# 04_POWER_LDO.net
KiCad netlist of a schematic drawn in Altium Designer
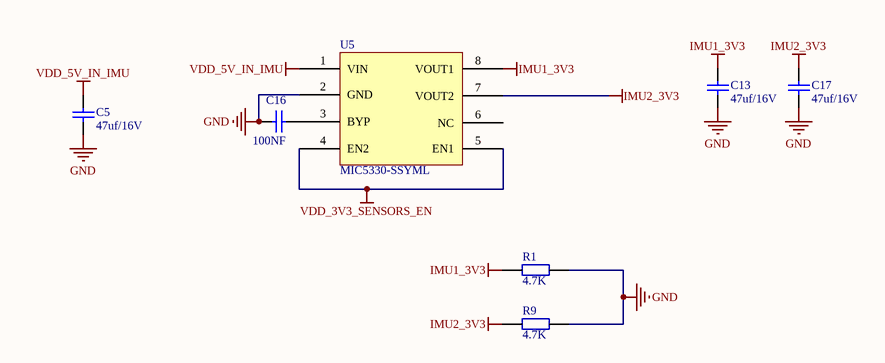
[diagram p0: 04_POWER_LDO.SchDoc]

(export (version "E")
  (design (tool "Eeschema 10.0.6"))
  (components
    (comp (ref "C5")
      (value "47uf/16V")
      (description "Capacitor")
      (libsource (lib "Miscellaneous Devices") (part "Cap"))
    )
    (comp (ref "C13")
      (value "47uf/16V")
      (description "Capacitor")
      (libsource (lib "Miscellaneous Devices") (part "Cap"))
    )
    (comp (ref "C16")
      (value "100NF")
      (fields (field (name "PUBLISHER") "Altium Limited"))
      (libsource (lib "Miscellaneous Devices") (part "Cap"))
    )
    (comp (ref "C17")
      (value "47uf/16V")
      (description "Capacitor")
      (libsource (lib "Miscellaneous Devices") (part "Cap"))
    )
    (comp (ref "R1")
      (value "4.7K")
      (footprint "0402R")
      (description "0402R1K 1%")
      (libsource (lib "CUAV") (part "0402R1K"))
    )
    (comp (ref "R9")
      (value "4.7K")
      (footprint "0402R")
      (description "0402R1K 1%")
      (libsource (lib "CUAV") (part "0402R1K"))
    )
    (comp (ref "U5") (value "MIC5330-SSYML") (footprint "MIC5530") (libsource (lib "hack") (part "MIC5530")))
  )
  (nets
    (net (code "1") (name "GND") (class "Default")
      (node (ref "C13") (pin "2") (pinfunction "2_2") (pintype "passive"))
      (node (ref "C16") (pin "2") (pinfunction "2_2") (pintype "passive"))
      (node (ref "C17") (pin "2") (pinfunction "2_2") (pintype "passive"))
      (node (ref "C5") (pin "2") (pinfunction "2_2") (pintype "passive"))
      (node (ref "R1") (pin "1") (pintype "passive"))
      (node (ref "R9") (pin "1") (pintype "passive"))
      (node (ref "U5") (pin "2") (pinfunction "GND_2") (pintype "passive"))
    )
    (net (code "2") (name "IMU1_3V3") (class "Default")
      (node (ref "C13") (pin "1") (pinfunction "1_1") (pintype "passive"))
      (node (ref "R1") (pin "2") (pintype "passive"))
      (node (ref "U5") (pin "8") (pinfunction "VOUT1_8") (pintype "passive"))
    )
    (net (code "3") (name "IMU2_3V3") (class "Default")
      (node (ref "C17") (pin "1") (pinfunction "1_1") (pintype "passive"))
      (node (ref "R9") (pin "2") (pintype "passive"))
      (node (ref "U5") (pin "7") (pinfunction "VOUT2_7") (pintype "passive"))
    )
    (net (code "4") (name "Net-(U5-BYP)") (class "Default")
      (node (ref "C16") (pin "1") (pinfunction "1_1") (pintype "passive"))
      (node (ref "U5") (pin "3") (pinfunction "BYP_3") (pintype "passive"))
    )
    (net (code "5") (name "VDD_3V3_SENSORS_EN") (class "Default")
      (node (ref "U5") (pin "4") (pinfunction "EN2_4") (pintype "passive"))
      (node (ref "U5") (pin "5") (pinfunction "EN1_5") (pintype "passive"))
    )
    (net (code "6") (name "VDD_5V_IN_IMU") (class "Default")
      (node (ref "C5") (pin "1") (pinfunction "1_1") (pintype "passive"))
      (node (ref "U5") (pin "1") (pinfunction "VIN_1") (pintype "passive"))
    )
    (net (code "7") (name "unconnected-(U5-NC-Pad6)") (class "Default")
      (node (ref "U5") (pin "6") (pinfunction "NC_6") (pintype "passive"))
    )
  )
)
